# easyeda-gba-sp-usb-c-schematic.net
KiCad netlist of a schematic drawn in EasyEDA
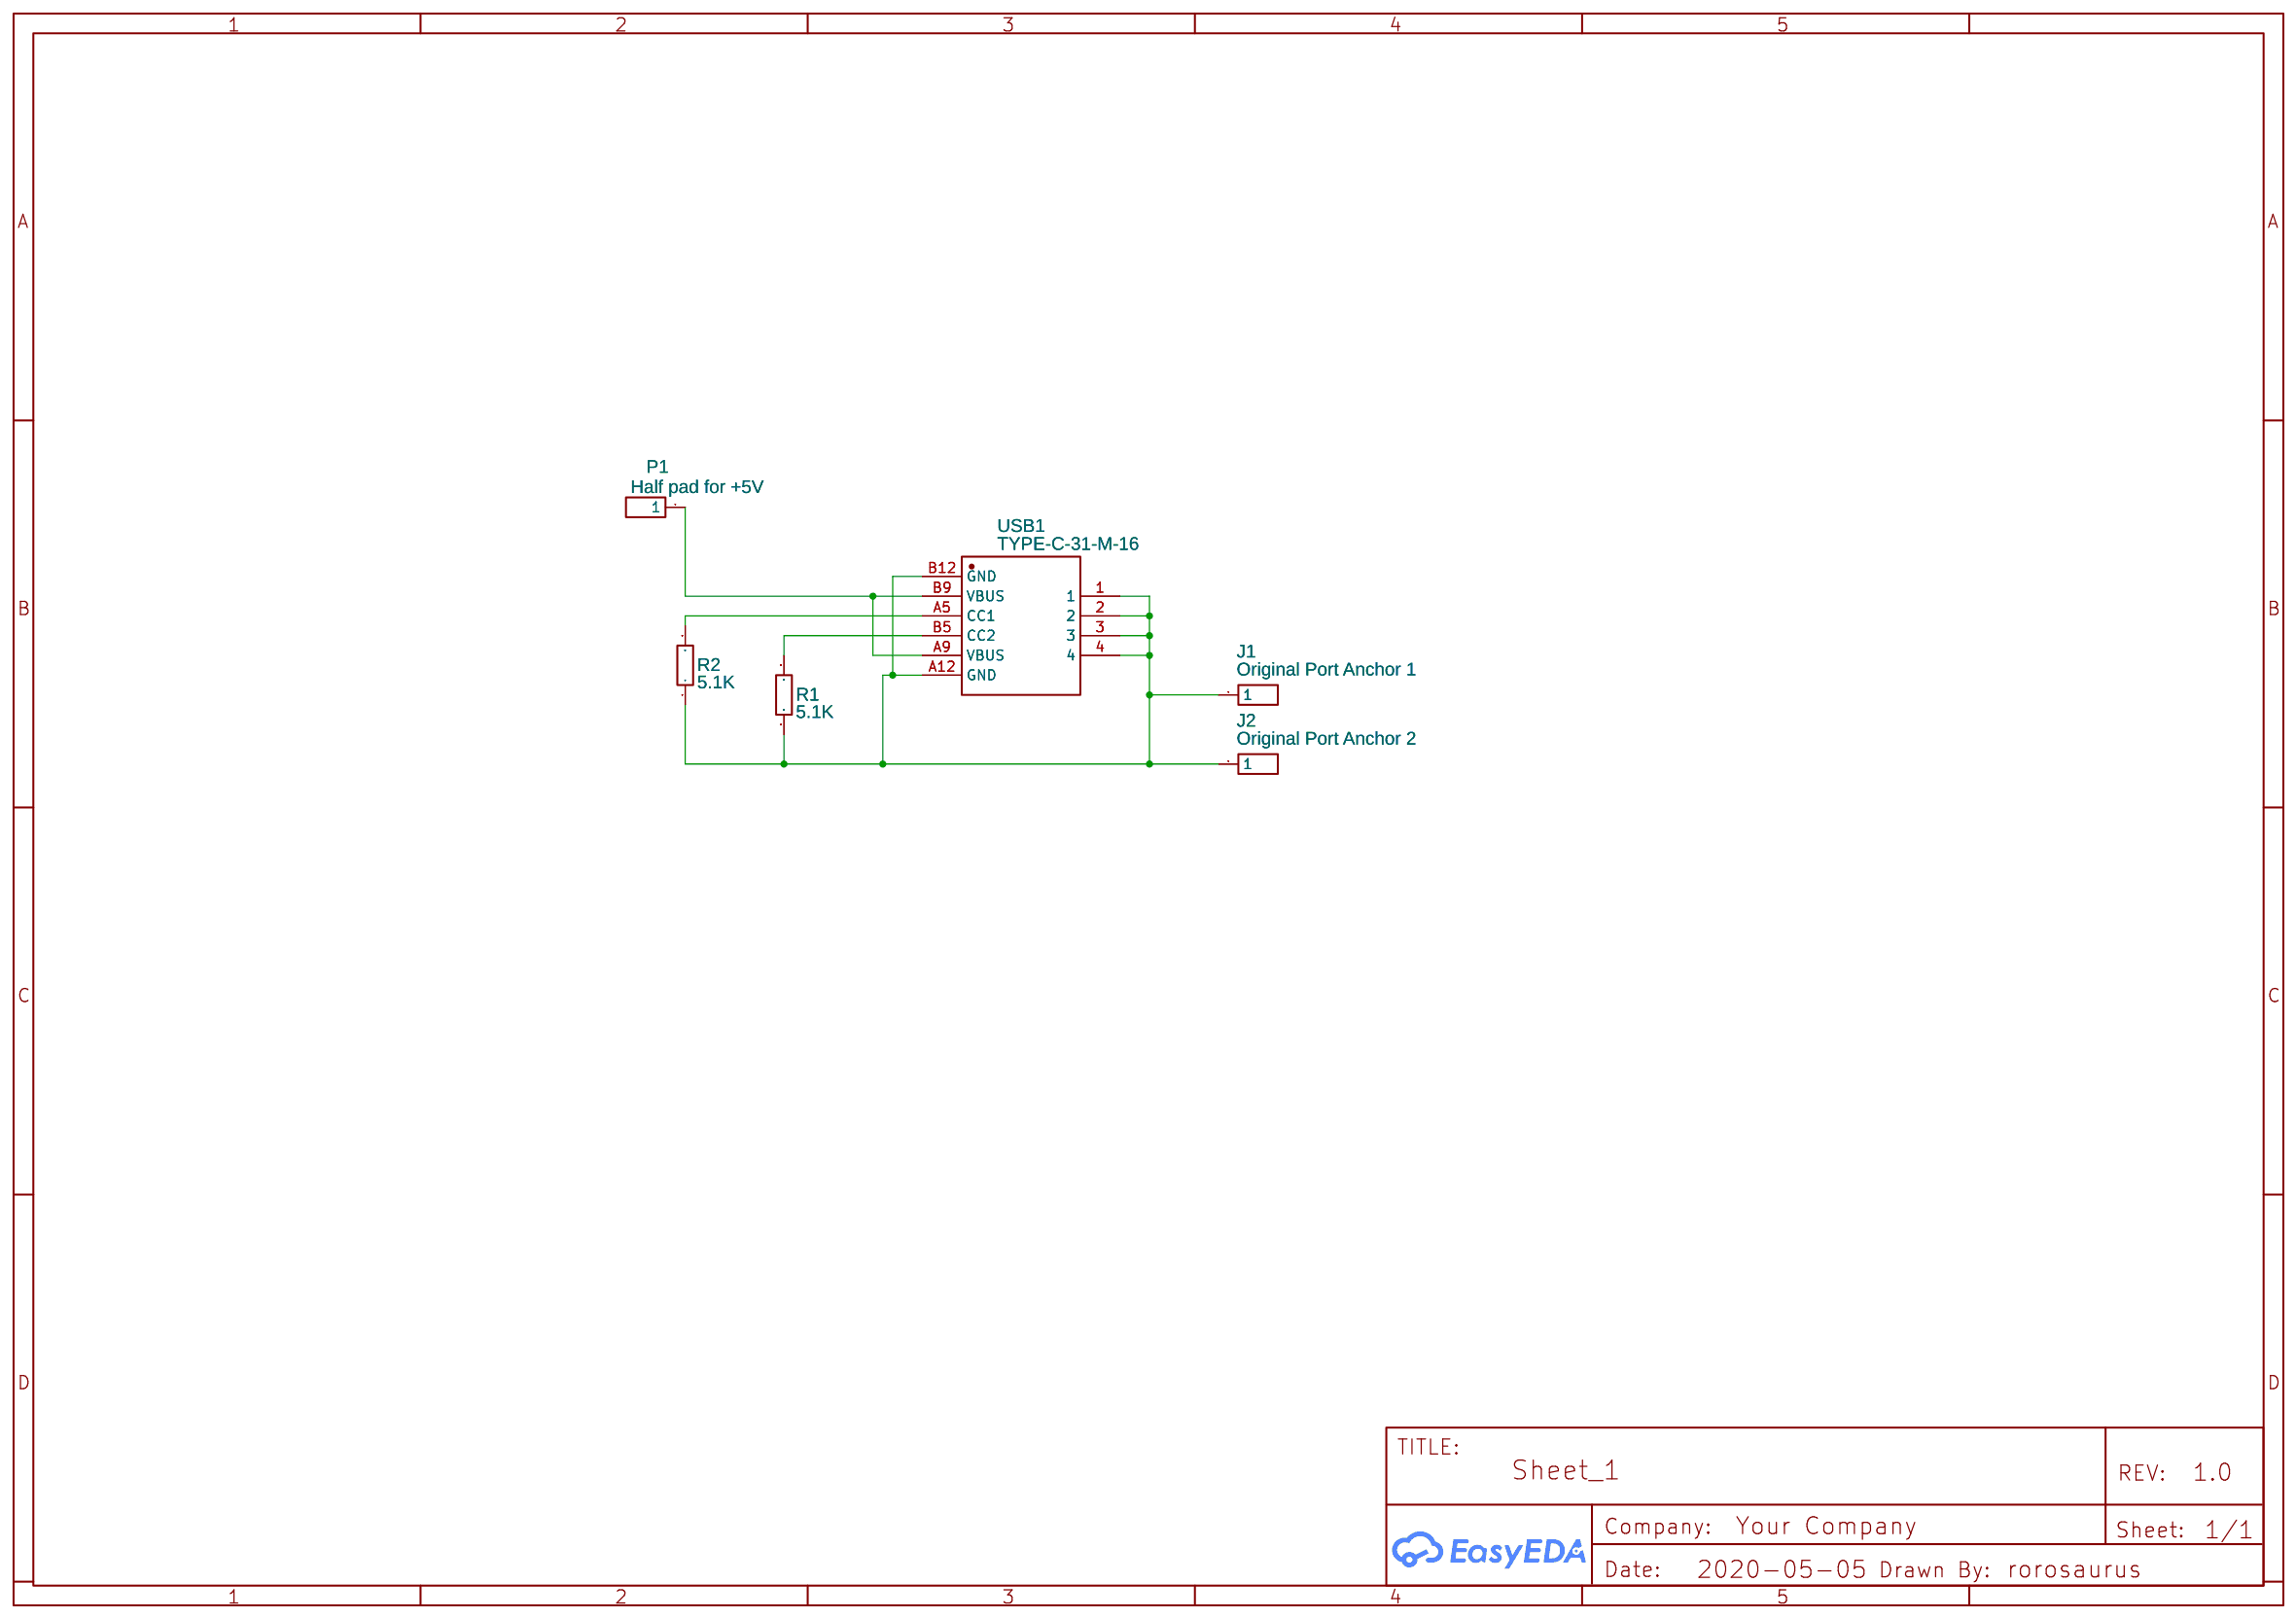
[diagram p0: schematic sheet]

(export (version "E")
  (design (tool "Eeschema 10.0.6"))
  (components
    (comp (ref "J1")
      (value "Original Port Anchor 1")
      (fields (field (name "BOM_Supplier Part") "C81276"))
      (libsource (lib "") (part "HDR-M-2.54_1x1"))
    )
    (comp (ref "J2")
      (value "Original Port Anchor 2")
      (fields (field (name "BOM_Supplier Part") "C81276"))
      (libsource (lib "") (part "HDR-M-2.54_1x1"))
    )
    (comp (ref "P1")
      (value "Half pad for +5V")
      (fields
        (field (name "BOM_Manufacturer Part") "Header-Male-2.54_1x1")
        (field (name "BOM_Supplier Part") "C81276")
      )
      (libsource (lib "") (part "Unknown_325_250"))
    )
    (comp (ref "R1")
      (value "5.1K")
      (fields
        (field (name "BOM_Manufacturer Part") "RMC04025.1K5%N")
        (field (name "BOM_Supplier Part") "C325524")
      )
      (libsource (lib "") (part "RMC04025.1K5%N"))
    )
    (comp (ref "R2")
      (value "5.1K")
      (fields
        (field (name "BOM_Manufacturer Part") "RMC04025.1K5%N")
        (field (name "BOM_Supplier Part") "C325524")
      )
      (libsource (lib "") (part "RMC04025.1K5%N"))
    )
    (comp (ref "USB1")
      (value "TYPE-C-31-M-16")
      (fields (field (name "BOM_Supplier Part") "C283541"))
      (libsource (lib "") (part "Unknown_510_315"))
    )
  )
  (nets
    (net (code "1") (name "Net-(J1-Pad1)") (class "Default")
      (node (ref "J1") (pin "1") (pinfunction "1_1") (pintype "input"))
      (node (ref "J2") (pin "1") (pinfunction "1_1") (pintype "input"))
      (node (ref "R1") (pin "1") (pinfunction "1_1") (pintype "unspecified"))
      (node (ref "R2") (pin "1") (pinfunction "1_1") (pintype "unspecified"))
      (node (ref "USB1") (pin "1") (pinfunction "1_1") (pintype "unspecified"))
      (node (ref "USB1") (pin "2") (pinfunction "2_2") (pintype "unspecified"))
      (node (ref "USB1") (pin "3") (pinfunction "3_3") (pintype "unspecified"))
      (node (ref "USB1") (pin "4") (pinfunction "4_4") (pintype "unspecified"))
      (node (ref "USB1") (pin "A12") (pinfunction "GND_A12") (pintype "unspecified"))
      (node (ref "USB1") (pin "B12") (pinfunction "GND_B12") (pintype "unspecified"))
    )
    (net (code "2") (name "Net-(P1-Pad1)") (class "Default")
      (node (ref "P1") (pin "1") (pinfunction "1_1") (pintype "input"))
      (node (ref "USB1") (pin "A9") (pinfunction "VBUS_A9") (pintype "unspecified"))
      (node (ref "USB1") (pin "B9") (pinfunction "VBUS_B9") (pintype "unspecified"))
    )
    (net (code "3") (name "Net-(USB1-CC1)") (class "Default")
      (node (ref "R2") (pin "2") (pinfunction "2_2") (pintype "unspecified"))
      (node (ref "USB1") (pin "A5") (pinfunction "CC1_A5") (pintype "unspecified"))
    )
    (net (code "4") (name "Net-(USB1-CC2)") (class "Default")
      (node (ref "R1") (pin "2") (pinfunction "2_2") (pintype "unspecified"))
      (node (ref "USB1") (pin "B5") (pinfunction "CC2_B5") (pintype "unspecified"))
    )
  )
)
